# AVRPADPTR.net
KiCad netlist of a schematic drawn in EAGLE
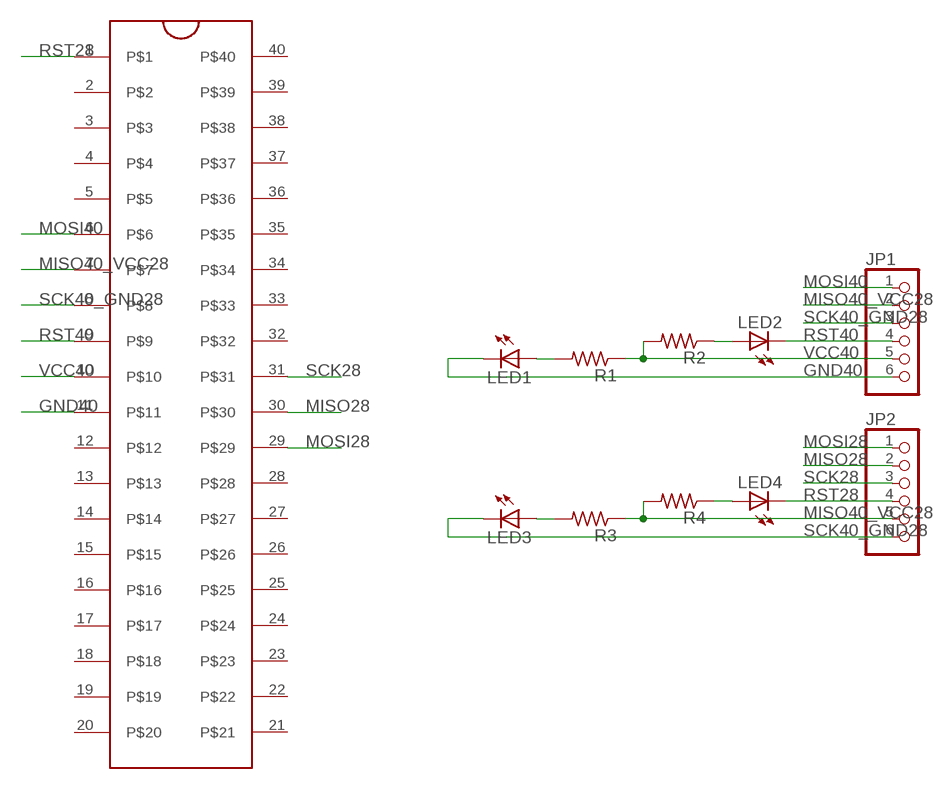
[diagram p0: schematic, sheet 1]

(export (version "E")
  (design (tool "Eeschema 10.0.6"))
  (components
    (comp (ref "JP1")
      (value "PINHD-1X6/90")
      (footprint "eagle-import:1X06_90")
      (libsource (lib "eagle-import") (part "PINHD-1X6/90"))
    )
    (comp (ref "JP2")
      (value "PINHD-1X6/90")
      (footprint "eagle-import:1X06_90")
      (libsource (lib "eagle-import") (part "PINHD-1X6/90"))
    )
    (comp (ref "LED1")
      (value "LED3MM")
      (footprint "eagle-import:LED3MM")
      (libsource (lib "eagle-import") (part "LED3MM"))
    )
    (comp (ref "LED2")
      (value "LED3MM")
      (footprint "eagle-import:LED3MM")
      (libsource (lib "eagle-import") (part "LED3MM"))
    )
    (comp (ref "LED3")
      (value "LED3MM")
      (footprint "eagle-import:LED3MM")
      (libsource (lib "eagle-import") (part "LED3MM"))
    )
    (comp (ref "LED4")
      (value "LED3MM")
      (footprint "eagle-import:LED3MM")
      (libsource (lib "eagle-import") (part "LED3MM"))
    )
    (comp (ref "R1")
      (value "R-US_0207/7")
      (footprint "eagle-import:0207_7")
      (libsource (lib "eagle-import") (part "R-US_0207/7"))
    )
    (comp (ref "R2")
      (value "R-US_0207/7")
      (footprint "eagle-import:0207_7")
      (libsource (lib "eagle-import") (part "R-US_0207/7"))
    )
    (comp (ref "R3")
      (value "R-US_0207/7")
      (footprint "eagle-import:0207_7")
      (libsource (lib "eagle-import") (part "R-US_0207/7"))
    )
    (comp (ref "R4")
      (value "R-US_0207/7")
      (footprint "eagle-import:0207_7")
      (libsource (lib "eagle-import") (part "R-US_0207/7"))
    )
    (comp (ref "U$1")
      (value "ZIFSOCKET-40-6DIL40-6-ZIF_SOCKET")
      (footprint "eagle-import:DIL40-6-ZIF_SOCKET")
      (libsource (lib "eagle-import") (part "ZIFSOCKET-40-6DIL40-6-ZIF_SOCKET"))
    )
  )
  (nets
    (net (code "1") (name "/GND40") (class "Default")
      (node (ref "JP1") (pin "6") (pinfunction "6_6") (pintype "passive"))
      (node (ref "LED1") (pin "K") (pinfunction "C_K") (pintype "passive"))
      (node (ref "U$1") (pin "11") (pinfunction "P$11_11") (pintype "bidirectional"))
    )
    (net (code "2") (name "/MISO28") (class "Default")
      (node (ref "JP2") (pin "2") (pinfunction "2_2") (pintype "passive"))
      (node (ref "U$1") (pin "30") (pinfunction "P$30_30") (pintype "bidirectional"))
    )
    (net (code "3") (name "/MISO40_VCC28") (class "Default")
      (node (ref "JP1") (pin "2") (pinfunction "2_2") (pintype "passive"))
      (node (ref "JP2") (pin "5") (pinfunction "5_5") (pintype "passive"))
      (node (ref "R3") (pin "1") (pinfunction "1_1") (pintype "passive"))
      (node (ref "R4") (pin "2") (pinfunction "2_2") (pintype "passive"))
      (node (ref "U$1") (pin "7") (pinfunction "P$7_7") (pintype "bidirectional"))
    )
    (net (code "4") (name "/MOSI28") (class "Default")
      (node (ref "JP2") (pin "1") (pinfunction "1_1") (pintype "passive"))
      (node (ref "U$1") (pin "29") (pinfunction "P$29_29") (pintype "bidirectional"))
    )
    (net (code "5") (name "/MOSI40") (class "Default")
      (node (ref "JP1") (pin "1") (pinfunction "1_1") (pintype "passive"))
      (node (ref "U$1") (pin "6") (pinfunction "P$6_6") (pintype "bidirectional"))
    )
    (net (code "6") (name "/RST28") (class "Default")
      (node (ref "JP2") (pin "4") (pinfunction "4_4") (pintype "passive"))
      (node (ref "LED4") (pin "K") (pinfunction "C_K") (pintype "passive"))
      (node (ref "U$1") (pin "1") (pinfunction "P$1_1") (pintype "bidirectional"))
    )
    (net (code "7") (name "/RST40") (class "Default")
      (node (ref "JP1") (pin "4") (pinfunction "4_4") (pintype "passive"))
      (node (ref "LED2") (pin "K") (pinfunction "C_K") (pintype "passive"))
      (node (ref "U$1") (pin "9") (pinfunction "P$9_9") (pintype "bidirectional"))
    )
    (net (code "8") (name "/SCK28") (class "Default")
      (node (ref "JP2") (pin "3") (pinfunction "3_3") (pintype "passive"))
      (node (ref "U$1") (pin "31") (pinfunction "P$31_31") (pintype "bidirectional"))
    )
    (net (code "9") (name "/SCK40_GND28") (class "Default")
      (node (ref "JP1") (pin "3") (pinfunction "3_3") (pintype "passive"))
      (node (ref "JP2") (pin "6") (pinfunction "6_6") (pintype "passive"))
      (node (ref "LED3") (pin "K") (pinfunction "C_K") (pintype "passive"))
      (node (ref "U$1") (pin "8") (pinfunction "P$8_8") (pintype "bidirectional"))
    )
    (net (code "10") (name "/VCC40") (class "Default")
      (node (ref "JP1") (pin "5") (pinfunction "5_5") (pintype "passive"))
      (node (ref "R1") (pin "1") (pinfunction "1_1") (pintype "passive"))
      (node (ref "R2") (pin "2") (pinfunction "2_2") (pintype "passive"))
      (node (ref "U$1") (pin "10") (pinfunction "P$10_10") (pintype "bidirectional"))
    )
    (net (code "11") (name "Net-(LED1-PadA)") (class "Default")
      (node (ref "LED1") (pin "A") (pinfunction "A_A") (pintype "passive"))
      (node (ref "R1") (pin "2") (pinfunction "2_2") (pintype "passive"))
    )
    (net (code "12") (name "Net-(LED2-PadA)") (class "Default")
      (node (ref "LED2") (pin "A") (pinfunction "A_A") (pintype "passive"))
      (node (ref "R2") (pin "1") (pinfunction "1_1") (pintype "passive"))
    )
    (net (code "13") (name "Net-(LED3-PadA)") (class "Default")
      (node (ref "LED3") (pin "A") (pinfunction "A_A") (pintype "passive"))
      (node (ref "R3") (pin "2") (pinfunction "2_2") (pintype "passive"))
    )
    (net (code "14") (name "Net-(LED4-PadA)") (class "Default")
      (node (ref "LED4") (pin "A") (pinfunction "A_A") (pintype "passive"))
      (node (ref "R4") (pin "1") (pinfunction "1_1") (pintype "passive"))
    )
    (net (code "15") (name "unconnected-(U$1-P$2-Pad2)") (class "Default")
      (node (ref "U$1") (pin "2") (pinfunction "P$2_2") (pintype "bidirectional"))
    )
    (net (code "16") (name "unconnected-(U$1-P$3-Pad3)") (class "Default")
      (node (ref "U$1") (pin "3") (pinfunction "P$3_3") (pintype "bidirectional"))
    )
    (net (code "17") (name "unconnected-(U$1-P$4-Pad4)") (class "Default")
      (node (ref "U$1") (pin "4") (pinfunction "P$4_4") (pintype "bidirectional"))
    )
    (net (code "18") (name "unconnected-(U$1-P$5-Pad5)") (class "Default")
      (node (ref "U$1") (pin "5") (pinfunction "P$5_5") (pintype "bidirectional"))
    )
    (net (code "19") (name "unconnected-(U$1-P$12-Pad12)") (class "Default")
      (node (ref "U$1") (pin "12") (pinfunction "P$12_12") (pintype "bidirectional"))
    )
    (net (code "20") (name "unconnected-(U$1-P$13-Pad13)") (class "Default")
      (node (ref "U$1") (pin "13") (pinfunction "P$13_13") (pintype "bidirectional"))
    )
    (net (code "21") (name "unconnected-(U$1-P$14-Pad14)") (class "Default")
      (node (ref "U$1") (pin "14") (pinfunction "P$14_14") (pintype "bidirectional"))
    )
    (net (code "22") (name "unconnected-(U$1-P$15-Pad15)") (class "Default")
      (node (ref "U$1") (pin "15") (pinfunction "P$15_15") (pintype "bidirectional"))
    )
    (net (code "23") (name "unconnected-(U$1-P$16-Pad16)") (class "Default")
      (node (ref "U$1") (pin "16") (pinfunction "P$16_16") (pintype "bidirectional"))
    )
    (net (code "24") (name "unconnected-(U$1-P$17-Pad17)") (class "Default")
      (node (ref "U$1") (pin "17") (pinfunction "P$17_17") (pintype "bidirectional"))
    )
    (net (code "25") (name "unconnected-(U$1-P$18-Pad18)") (class "Default")
      (node (ref "U$1") (pin "18") (pinfunction "P$18_18") (pintype "bidirectional"))
    )
    (net (code "26") (name "unconnected-(U$1-P$19-Pad19)") (class "Default")
      (node (ref "U$1") (pin "19") (pinfunction "P$19_19") (pintype "bidirectional"))
    )
    (net (code "27") (name "unconnected-(U$1-P$20-Pad20)") (class "Default")
      (node (ref "U$1") (pin "20") (pinfunction "P$20_20") (pintype "bidirectional"))
    )
    (net (code "28") (name "unconnected-(U$1-P$21-Pad21)") (class "Default")
      (node (ref "U$1") (pin "21") (pinfunction "P$21_21") (pintype "bidirectional"))
    )
    (net (code "29") (name "unconnected-(U$1-P$22-Pad22)") (class "Default")
      (node (ref "U$1") (pin "22") (pinfunction "P$22_22") (pintype "bidirectional"))
    )
    (net (code "30") (name "unconnected-(U$1-P$23-Pad23)") (class "Default")
      (node (ref "U$1") (pin "23") (pinfunction "P$23_23") (pintype "bidirectional"))
    )
    (net (code "31") (name "unconnected-(U$1-P$24-Pad24)") (class "Default")
      (node (ref "U$1") (pin "24") (pinfunction "P$24_24") (pintype "bidirectional"))
    )
    (net (code "32") (name "unconnected-(U$1-P$25-Pad25)") (class "Default")
      (node (ref "U$1") (pin "25") (pinfunction "P$25_25") (pintype "bidirectional"))
    )
    (net (code "33") (name "unconnected-(U$1-P$26-Pad26)") (class "Default")
      (node (ref "U$1") (pin "26") (pinfunction "P$26_26") (pintype "bidirectional"))
    )
    (net (code "34") (name "unconnected-(U$1-P$27-Pad27)") (class "Default")
      (node (ref "U$1") (pin "27") (pinfunction "P$27_27") (pintype "bidirectional"))
    )
    (net (code "35") (name "unconnected-(U$1-P$28-Pad28)") (class "Default")
      (node (ref "U$1") (pin "28") (pinfunction "P$28_28") (pintype "bidirectional"))
    )
    (net (code "36") (name "unconnected-(U$1-P$32-Pad32)") (class "Default")
      (node (ref "U$1") (pin "32") (pinfunction "P$32_32") (pintype "bidirectional"))
    )
    (net (code "37") (name "unconnected-(U$1-P$33-Pad33)") (class "Default")
      (node (ref "U$1") (pin "33") (pinfunction "P$33_33") (pintype "bidirectional"))
    )
    (net (code "38") (name "unconnected-(U$1-P$34-Pad34)") (class "Default")
      (node (ref "U$1") (pin "34") (pinfunction "P$34_34") (pintype "bidirectional"))
    )
    (net (code "39") (name "unconnected-(U$1-P$35-Pad35)") (class "Default")
      (node (ref "U$1") (pin "35") (pinfunction "P$35_35") (pintype "bidirectional"))
    )
    (net (code "40") (name "unconnected-(U$1-P$36-Pad36)") (class "Default")
      (node (ref "U$1") (pin "36") (pinfunction "P$36_36") (pintype "bidirectional"))
    )
    (net (code "41") (name "unconnected-(U$1-P$37-Pad37)") (class "Default")
      (node (ref "U$1") (pin "37") (pinfunction "P$37_37") (pintype "bidirectional"))
    )
    (net (code "42") (name "unconnected-(U$1-P$38-Pad38)") (class "Default")
      (node (ref "U$1") (pin "38") (pinfunction "P$38_38") (pintype "bidirectional"))
    )
    (net (code "43") (name "unconnected-(U$1-P$39-Pad39)") (class "Default")
      (node (ref "U$1") (pin "39") (pinfunction "P$39_39") (pintype "bidirectional"))
    )
    (net (code "44") (name "unconnected-(U$1-P$40-Pad40)") (class "Default")
      (node (ref "U$1") (pin "40") (pinfunction "P$40_40") (pintype "bidirectional"))
    )
  )
)
